# 400D_Audio-LED.net
KiCad netlist of a schematic drawn in EAGLE
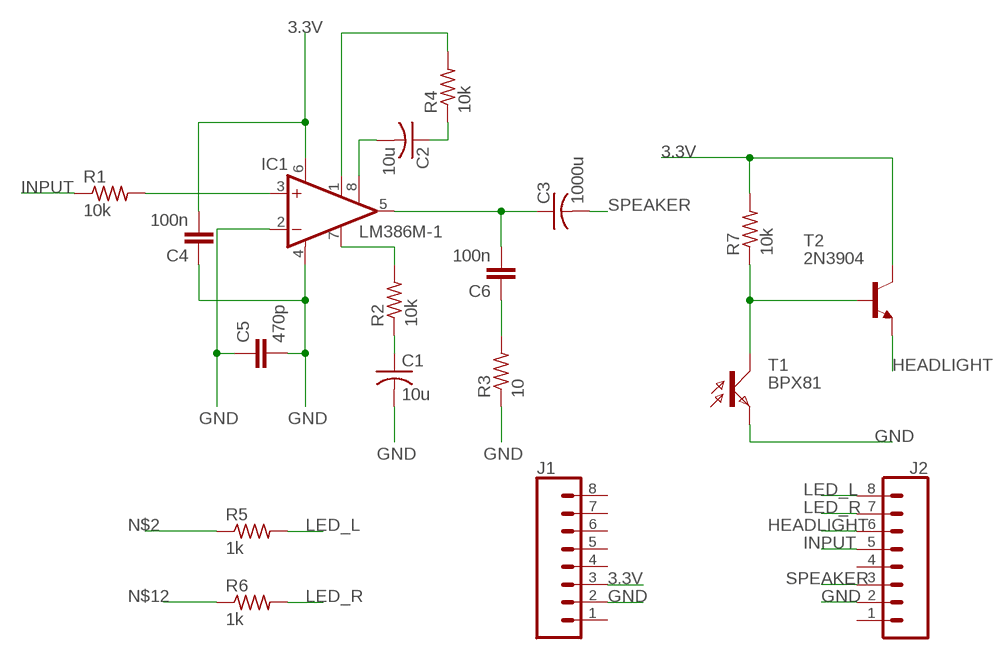
[diagram p0: schematic, sheet 1]

(export (version "E")
  (design (tool "Eeschema 10.0.6"))
  (components
    (comp (ref "C1")
      (value "10u")
      (footprint "eagle-import:C0805")
      (libsource (lib "eagle-import") (part "C-USC0805"))
    )
    (comp (ref "C2")
      (value "10u")
      (footprint "eagle-import:C0805")
      (libsource (lib "eagle-import") (part "C-USC0805"))
    )
    (comp (ref "C3")
      (value "1000u")
      (footprint "eagle-import:C0805")
      (libsource (lib "eagle-import") (part "C-USC0805"))
    )
    (comp (ref "C4")
      (value "100n")
      (footprint "eagle-import:C0805")
      (libsource (lib "eagle-import") (part "C-EUC0805"))
    )
    (comp (ref "C5")
      (value "470p")
      (footprint "eagle-import:C0805")
      (libsource (lib "eagle-import") (part "C-EUC0805"))
    )
    (comp (ref "C6")
      (value "100n")
      (footprint "eagle-import:C0805")
      (libsource (lib "eagle-import") (part "C-EUC0805"))
    )
    (comp (ref "IC1")
      (value "LM386M-1")
      (footprint "eagle-import:SO08")
      (libsource (lib "eagle-import") (part "LM386?-M1"))
    )
    (comp (ref "J1")
      (value "CONN_08\"")
      (footprint "eagle-import:1X08")
      (libsource (lib "eagle-import") (part "CONN_08{dblquote}"))
    )
    (comp (ref "J2")
      (value "CONN_08\"")
      (footprint "eagle-import:1X08")
      (libsource (lib "eagle-import") (part "CONN_08{dblquote}"))
    )
    (comp (ref "R1")
      (value "10k")
      (footprint "eagle-import:R0805")
      (libsource (lib "eagle-import") (part "R-US_R0805"))
    )
    (comp (ref "R2")
      (value "10k")
      (footprint "eagle-import:R0805")
      (libsource (lib "eagle-import") (part "R-US_R0805"))
    )
    (comp (ref "R3")
      (value "10")
      (footprint "eagle-import:R0805")
      (libsource (lib "eagle-import") (part "R-US_R0805"))
    )
    (comp (ref "R4")
      (value "10k")
      (footprint "eagle-import:R0805")
      (libsource (lib "eagle-import") (part "R-US_R0805"))
    )
    (comp (ref "R5")
      (value "1k")
      (footprint "eagle-import:R0805")
      (libsource (lib "eagle-import") (part "R-US_R0805"))
    )
    (comp (ref "R6")
      (value "1k")
      (footprint "eagle-import:R0805")
      (libsource (lib "eagle-import") (part "R-US_R0805"))
    )
    (comp (ref "R7")
      (value "10k")
      (footprint "eagle-import:R0805")
      (libsource (lib "eagle-import") (part "R-US_R0805"))
    )
    (comp (ref "T1")
      (value "BPX81")
      (footprint "eagle-import:BPX81")
      (libsource (lib "eagle-import") (part "BPX81"))
    )
    (comp (ref "T2")
      (value "2N3904")
      (footprint "eagle-import:TO92")
      (libsource (lib "eagle-import") (part "2N3904"))
    )
  )
  (nets
    (net (code "1") (name "/3.3V") (class "Default")
      (node (ref "C4") (pin "2") (pinfunction "2_2") (pintype "passive"))
      (node (ref "IC1") (pin "6") (pinfunction "VS_6") (pintype "power_in"))
      (node (ref "J1") (pin "3") (pinfunction "3_3") (pintype "passive"))
      (node (ref "R7") (pin "2") (pinfunction "2_2") (pintype "passive"))
      (node (ref "T2") (pin "1") (pinfunction "C_1") (pintype "passive"))
    )
    (net (code "2") (name "/GND") (class "Default")
      (node (ref "C1") (pin "2") (pinfunction "2_2") (pintype "passive"))
      (node (ref "C4") (pin "1") (pinfunction "1_1") (pintype "passive"))
      (node (ref "C5") (pin "1") (pinfunction "1_1") (pintype "passive"))
      (node (ref "C5") (pin "2") (pinfunction "2_2") (pintype "passive"))
      (node (ref "IC1") (pin "2") (pinfunction "-IN_2") (pintype "input"))
      (node (ref "IC1") (pin "4") (pinfunction "GND_4") (pintype "power_in"))
      (node (ref "J1") (pin "2") (pinfunction "2_2") (pintype "passive"))
      (node (ref "J2") (pin "2") (pinfunction "2_2") (pintype "passive"))
      (node (ref "R3") (pin "1") (pinfunction "1_1") (pintype "passive"))
      (node (ref "T1") (pin "E") (pinfunction "E_E") (pintype "passive"))
    )
    (net (code "3") (name "/HEADLIGHT") (class "Default")
      (node (ref "J2") (pin "6") (pinfunction "6_6") (pintype "passive"))
      (node (ref "T2") (pin "3") (pinfunction "E_3") (pintype "passive"))
    )
    (net (code "4") (name "/INPUT") (class "Default")
      (node (ref "J2") (pin "5") (pinfunction "5_5") (pintype "passive"))
      (node (ref "R1") (pin "1") (pinfunction "1_1") (pintype "passive"))
    )
    (net (code "5") (name "/LED_L") (class "Default")
      (node (ref "J2") (pin "8") (pinfunction "8_8") (pintype "passive"))
      (node (ref "R5") (pin "2") (pinfunction "2_2") (pintype "passive"))
    )
    (net (code "6") (name "/LED_R") (class "Default")
      (node (ref "J2") (pin "7") (pinfunction "7_7") (pintype "passive"))
      (node (ref "R6") (pin "2") (pinfunction "2_2") (pintype "passive"))
    )
    (net (code "7") (name "/N$2") (class "Default")
      (node (ref "R5") (pin "1") (pinfunction "1_1") (pintype "passive"))
    )
    (net (code "8") (name "/N$12") (class "Default")
      (node (ref "R6") (pin "1") (pinfunction "1_1") (pintype "passive"))
    )
    (net (code "9") (name "/SPEAKER") (class "Default")
      (node (ref "C3") (pin "2") (pinfunction "2_2") (pintype "passive"))
      (node (ref "J2") (pin "3") (pinfunction "3_3") (pintype "passive"))
    )
    (net (code "10") (name "Net-(C1-Pad1)") (class "Default")
      (node (ref "C1") (pin "1") (pinfunction "1_1") (pintype "passive"))
      (node (ref "R2") (pin "1") (pinfunction "1_1") (pintype "passive"))
    )
    (net (code "11") (name "Net-(C2-Pad1)") (class "Default")
      (node (ref "C2") (pin "1") (pinfunction "1_1") (pintype "passive"))
      (node (ref "R4") (pin "1") (pinfunction "1_1") (pintype "passive"))
    )
    (net (code "12") (name "Net-(C2-Pad2)") (class "Default")
      (node (ref "C2") (pin "2") (pinfunction "2_2") (pintype "passive"))
      (node (ref "IC1") (pin "8") (pinfunction "GAIN_8") (pintype "passive"))
    )
    (net (code "13") (name "Net-(C6-Pad1)") (class "Default")
      (node (ref "C6") (pin "1") (pinfunction "1_1") (pintype "passive"))
      (node (ref "R3") (pin "2") (pinfunction "2_2") (pintype "passive"))
    )
    (net (code "14") (name "Net-(IC1-+IN)") (class "Default")
      (node (ref "IC1") (pin "3") (pinfunction "+IN_3") (pintype "input"))
      (node (ref "R1") (pin "2") (pinfunction "2_2") (pintype "passive"))
    )
    (net (code "15") (name "Net-(IC1-BYPASS)") (class "Default")
      (node (ref "IC1") (pin "7") (pinfunction "BYPASS_7") (pintype "passive"))
      (node (ref "R2") (pin "2") (pinfunction "2_2") (pintype "passive"))
    )
    (net (code "16") (name "Net-(IC1-GAIN-Pad1)") (class "Default")
      (node (ref "IC1") (pin "1") (pinfunction "GAIN_1") (pintype "passive"))
      (node (ref "R4") (pin "2") (pinfunction "2_2") (pintype "passive"))
    )
    (net (code "17") (name "Net-(IC1-OUT)") (class "Default")
      (node (ref "C3") (pin "1") (pinfunction "1_1") (pintype "passive"))
      (node (ref "C6") (pin "2") (pinfunction "2_2") (pintype "passive"))
      (node (ref "IC1") (pin "5") (pinfunction "OUT_5") (pintype "output"))
    )
    (net (code "18") (name "Net-(T2-B)") (class "Default")
      (node (ref "R7") (pin "1") (pinfunction "1_1") (pintype "passive"))
      (node (ref "T1") (pin "C") (pinfunction "C_C") (pintype "passive"))
      (node (ref "T2") (pin "2") (pinfunction "B_2") (pintype "passive"))
    )
    (net (code "19") (name "unconnected-(J1-Pad1)") (class "Default")
      (node (ref "J1") (pin "1") (pinfunction "1_1") (pintype "passive"))
    )
    (net (code "20") (name "unconnected-(J1-Pad4)") (class "Default")
      (node (ref "J1") (pin "4") (pinfunction "4_4") (pintype "passive"))
    )
    (net (code "21") (name "unconnected-(J1-Pad5)") (class "Default")
      (node (ref "J1") (pin "5") (pinfunction "5_5") (pintype "passive"))
    )
    (net (code "22") (name "unconnected-(J1-Pad6)") (class "Default")
      (node (ref "J1") (pin "6") (pinfunction "6_6") (pintype "passive"))
    )
    (net (code "23") (name "unconnected-(J1-Pad7)") (class "Default")
      (node (ref "J1") (pin "7") (pinfunction "7_7") (pintype "passive"))
    )
    (net (code "24") (name "unconnected-(J1-Pad8)") (class "Default")
      (node (ref "J1") (pin "8") (pinfunction "8_8") (pintype "passive"))
    )
    (net (code "25") (name "unconnected-(J2-Pad1)") (class "Default")
      (node (ref "J2") (pin "1") (pinfunction "1_1") (pintype "passive"))
    )
    (net (code "26") (name "unconnected-(J2-Pad4)") (class "Default")
      (node (ref "J2") (pin "4") (pinfunction "4_4") (pintype "passive"))
    )
  )
)
